# MCU.net
KiCad netlist of a schematic drawn in Altium Designer
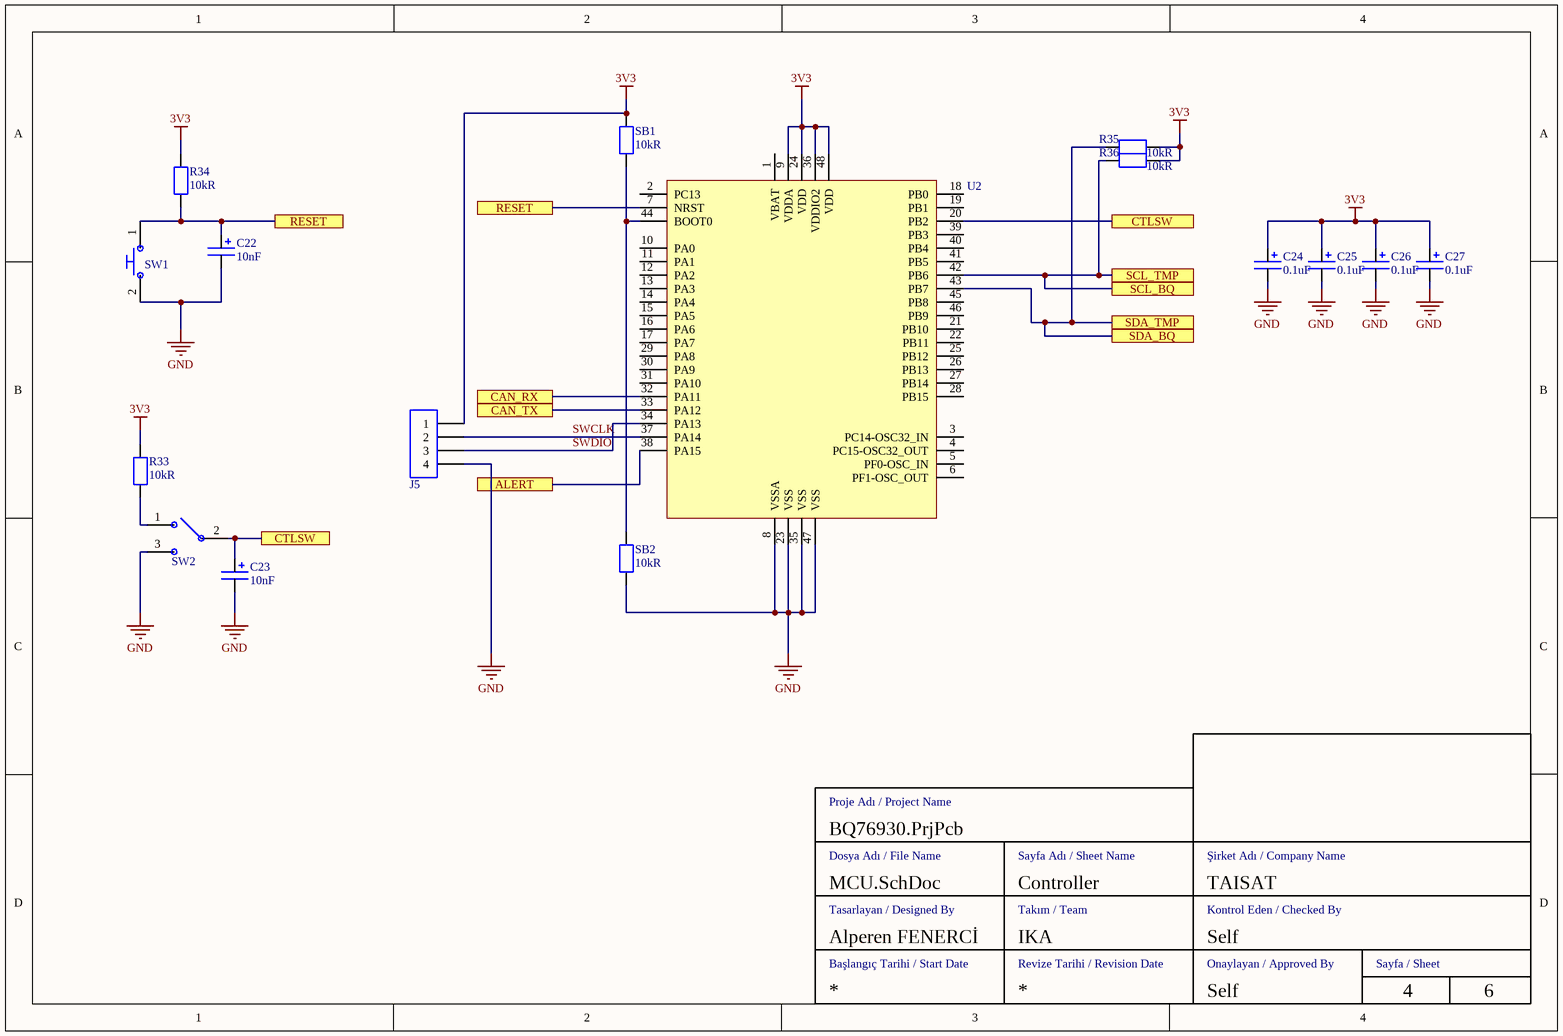
[diagram p0: MCU.SchDoc]

(export (version "E")
  (design (tool "Eeschema 10.0.6"))
  (components
    (comp (ref "C22")
      (value "10nF")
      (footprint "CAP 0603")
      (description "Multilayer Ceramic Capacitor")
      (fields (field (name "Comment") "CAP 0603"))
      (libsource (lib "Kaptanyums Lib") (part "CAP 0603"))
    )
    (comp (ref "C23")
      (value "10nF")
      (footprint "CAP 0603")
      (description "Multilayer Ceramic Capacitor")
      (fields (field (name "Comment") "CAP 0603"))
      (libsource (lib "Kaptanyums Lib") (part "CAP 0603"))
    )
    (comp (ref "C24")
      (value "0.1uF")
      (footprint "CAP 0603")
      (description "Multilayer Ceramic Capacitor")
      (fields (field (name "Comment") "CAP 0603"))
      (libsource (lib "Kaptanyums Lib") (part "CAP 0603"))
    )
    (comp (ref "C25")
      (value "0.1uF")
      (footprint "CAP 0603")
      (description "Multilayer Ceramic Capacitor")
      (fields (field (name "Comment") "CAP 0603"))
      (libsource (lib "Kaptanyums Lib") (part "CAP 0603"))
    )
    (comp (ref "C26")
      (value "0.1uF")
      (footprint "CAP 0603")
      (description "Multilayer Ceramic Capacitor")
      (fields (field (name "Comment") "CAP 0603"))
      (libsource (lib "Kaptanyums Lib") (part "CAP 0603"))
    )
    (comp (ref "C27")
      (value "0.1uF")
      (footprint "CAP 0603")
      (description "Multilayer Ceramic Capacitor")
      (fields (field (name "Comment") "CAP 0603"))
      (libsource (lib "Kaptanyums Lib") (part "CAP 0603"))
    )
    (comp (ref "J5")
      (value "146285-4")
      (footprint "HMATHT00C41")
      (description "Header for PCB")
      (libsource (lib "Kaptanyums Lib") (part "HMATHT00C41"))
    )
    (comp (ref "R33")
      (value "10kR")
      (footprint "RESISTOR 0603")
      (description "SMD Chip Resistor")
      (fields (field (name "Comment") "RES 0603"))
      (libsource (lib "Kaptanyums Lib") (part "RES 0603"))
    )
    (comp (ref "R34")
      (value "10kR")
      (footprint "RESISTOR 0603")
      (description "SMD Chip Resistor")
      (fields (field (name "Comment") "RES 0603"))
      (libsource (lib "Kaptanyums Lib") (part "RES 0603"))
    )
    (comp (ref "R35")
      (value "10kR")
      (footprint "RESISTOR 0603")
      (description "SMD Chip Resistor")
      (fields (field (name "Comment") "RES 0603"))
      (libsource (lib "Kaptanyums Lib") (part "RES 0603"))
    )
    (comp (ref "R36")
      (value "10kR")
      (footprint "RESISTOR 0603")
      (description "SMD Chip Resistor")
      (fields (field (name "Comment") "RES 0603"))
      (libsource (lib "Kaptanyums Lib") (part "RES 0603"))
    )
    (comp (ref "SB1")
      (value "10kR")
      (footprint "RESISTOR 0603")
      (description "SMD Chip Resistor")
      (fields (field (name "Comment") "RES 0603"))
      (libsource (lib "Kaptanyums Lib") (part "RES 0603"))
    )
    (comp (ref "SB2")
      (value "10kR")
      (footprint "RESISTOR 0603")
      (description "SMD Chip Resistor")
      (fields (field (name "Comment") "RES 0603"))
      (libsource (lib "Kaptanyums Lib") (part "RES 0603"))
    )
    (comp (ref "SW1")
      (value "DS1042-03")
      (footprint "SWITCH-6X6")
      (description "Switch")
      (libsource (lib "Kaptanyums Lib") (part "DS1042-03"))
    )
    (comp (ref "SW2")
      (value "L-KLS7-SS-12F20A")
      (footprint "SPDT")
      (description "Switch")
      (libsource (lib "Kaptanyums Lib") (part "L-KLS7-SS-12F20A"))
    )
    (comp (ref "U2")
      (value "STM32F072C8")
      (footprint "LQFP48")
      (description "STM32 ARM Cortex M0")
      (libsource (lib "Kaptanyums Lib") (part "STM32F072C8"))
    )
  )
  (nets
    (net (code "1") (name "/ALERT") (class "Default")
      (node (ref "U2") (pin "38") (pinfunction "PA15_38") (pintype "passive"))
    )
    (net (code "2") (name "/CAN_RX") (class "Default")
      (node (ref "U2") (pin "32") (pinfunction "PA11_32") (pintype "passive"))
    )
    (net (code "3") (name "/CAN_TX") (class "Default")
      (node (ref "U2") (pin "33") (pinfunction "PA12_33") (pintype "passive"))
    )
    (net (code "4") (name "/CTLSW") (class "Default")
      (node (ref "C23") (pin "1") (pinfunction "1_1") (pintype "passive"))
      (node (ref "SW2") (pin "2") (pinfunction "2_2") (pintype "passive"))
      (node (ref "U2") (pin "20") (pinfunction "PB2_20") (pintype "passive"))
    )
    (net (code "5") (name "/RESET") (class "Default")
      (node (ref "C22") (pin "1") (pinfunction "1_1") (pintype "passive"))
      (node (ref "R34") (pin "1") (pinfunction "1_1") (pintype "passive"))
      (node (ref "SW1") (pin "1") (pinfunction "1_1") (pintype "passive"))
      (node (ref "U2") (pin "7") (pinfunction "NRST_7") (pintype "passive"))
    )
    (net (code "6") (name "/SCL_BQ") (class "Default")
      (node (ref "R36") (pin "1") (pinfunction "1_1") (pintype "passive"))
      (node (ref "U2") (pin "42") (pinfunction "PB6_42") (pintype "passive"))
    )
    (net (code "7") (name "/SDA_BQ") (class "Default")
      (node (ref "R35") (pin "1") (pinfunction "1_1") (pintype "passive"))
      (node (ref "U2") (pin "43") (pinfunction "PB7_43") (pintype "passive"))
    )
    (net (code "8") (name "/SWCLK") (class "Default")
      (node (ref "J5") (pin "2") (pinfunction "2_2") (pintype "passive"))
      (node (ref "U2") (pin "37") (pinfunction "PA14_37") (pintype "passive"))
    )
    (net (code "9") (name "/SWDIO") (class "Default")
      (node (ref "J5") (pin "3") (pinfunction "3_3") (pintype "passive"))
      (node (ref "U2") (pin "34") (pinfunction "PA13_34") (pintype "passive"))
    )
    (net (code "10") (name "3V3") (class "Default")
      (node (ref "C24") (pin "1") (pinfunction "1_1") (pintype "passive"))
      (node (ref "C25") (pin "1") (pinfunction "1_1") (pintype "passive"))
      (node (ref "C26") (pin "1") (pinfunction "1_1") (pintype "passive"))
      (node (ref "C27") (pin "1") (pinfunction "1_1") (pintype "passive"))
      (node (ref "J5") (pin "1") (pinfunction "1_1") (pintype "passive"))
      (node (ref "R33") (pin "2") (pinfunction "2_2") (pintype "passive"))
      (node (ref "R34") (pin "2") (pinfunction "2_2") (pintype "passive"))
      (node (ref "R35") (pin "2") (pinfunction "2_2") (pintype "passive"))
      (node (ref "R36") (pin "2") (pinfunction "2_2") (pintype "passive"))
      (node (ref "SB1") (pin "2") (pinfunction "2_2") (pintype "passive"))
      (node (ref "U2") (pin "24") (pinfunction "VDD_24") (pintype "passive"))
      (node (ref "U2") (pin "36") (pinfunction "VDDIO2_36") (pintype "passive"))
      (node (ref "U2") (pin "48") (pinfunction "VDD_48") (pintype "passive"))
      (node (ref "U2") (pin "9") (pinfunction "VDDA_9") (pintype "passive"))
    )
    (net (code "11") (name "GND") (class "Default")
      (node (ref "C22") (pin "2") (pinfunction "2_2") (pintype "passive"))
      (node (ref "C23") (pin "2") (pinfunction "2_2") (pintype "passive"))
      (node (ref "C24") (pin "2") (pinfunction "2_2") (pintype "passive"))
      (node (ref "C25") (pin "2") (pinfunction "2_2") (pintype "passive"))
      (node (ref "C26") (pin "2") (pinfunction "2_2") (pintype "passive"))
      (node (ref "C27") (pin "2") (pinfunction "2_2") (pintype "passive"))
      (node (ref "J5") (pin "4") (pinfunction "4_4") (pintype "passive"))
      (node (ref "SB2") (pin "1") (pinfunction "1_1") (pintype "passive"))
      (node (ref "SW1") (pin "2") (pinfunction "2_2") (pintype "passive"))
      (node (ref "SW2") (pin "3") (pinfunction "3_3") (pintype "passive"))
      (node (ref "U2") (pin "23") (pinfunction "VSS_23") (pintype "passive"))
      (node (ref "U2") (pin "35") (pinfunction "VSS_35") (pintype "passive"))
      (node (ref "U2") (pin "47") (pinfunction "VSS_47") (pintype "passive"))
      (node (ref "U2") (pin "8") (pinfunction "VSSA_8") (pintype "passive"))
    )
    (net (code "12") (name "Net-(R33-Pad1)") (class "Default")
      (node (ref "R33") (pin "1") (pinfunction "1_1") (pintype "passive"))
      (node (ref "SW2") (pin "1") (pinfunction "1_1") (pintype "passive"))
    )
    (net (code "13") (name "Net-(U2-BOOT0)") (class "Default")
      (node (ref "SB1") (pin "1") (pinfunction "1_1") (pintype "passive"))
      (node (ref "SB2") (pin "2") (pinfunction "2_2") (pintype "passive"))
      (node (ref "U2") (pin "44") (pinfunction "BOOT0_44") (pintype "passive"))
    )
    (net (code "14") (name "unconnected-(U2-PA0-Pad10)") (class "Default")
      (node (ref "U2") (pin "10") (pinfunction "PA0_10") (pintype "passive"))
    )
    (net (code "15") (name "unconnected-(U2-PA1-Pad11)") (class "Default")
      (node (ref "U2") (pin "11") (pinfunction "PA1_11") (pintype "passive"))
    )
    (net (code "16") (name "unconnected-(U2-PA2-Pad12)") (class "Default")
      (node (ref "U2") (pin "12") (pinfunction "PA2_12") (pintype "passive"))
    )
    (net (code "17") (name "unconnected-(U2-PA3-Pad13)") (class "Default")
      (node (ref "U2") (pin "13") (pinfunction "PA3_13") (pintype "passive"))
    )
    (net (code "18") (name "unconnected-(U2-PA4-Pad14)") (class "Default")
      (node (ref "U2") (pin "14") (pinfunction "PA4_14") (pintype "passive"))
    )
    (net (code "19") (name "unconnected-(U2-PA5-Pad15)") (class "Default")
      (node (ref "U2") (pin "15") (pinfunction "PA5_15") (pintype "passive"))
    )
    (net (code "20") (name "unconnected-(U2-PA6-Pad16)") (class "Default")
      (node (ref "U2") (pin "16") (pinfunction "PA6_16") (pintype "passive"))
    )
    (net (code "21") (name "unconnected-(U2-PA7-Pad17)") (class "Default")
      (node (ref "U2") (pin "17") (pinfunction "PA7_17") (pintype "passive"))
    )
    (net (code "22") (name "unconnected-(U2-PA8-Pad29)") (class "Default")
      (node (ref "U2") (pin "29") (pinfunction "PA8_29") (pintype "passive"))
    )
    (net (code "23") (name "unconnected-(U2-PA9-Pad30)") (class "Default")
      (node (ref "U2") (pin "30") (pinfunction "PA9_30") (pintype "passive"))
    )
    (net (code "24") (name "unconnected-(U2-PA10-Pad31)") (class "Default")
      (node (ref "U2") (pin "31") (pinfunction "PA10_31") (pintype "passive"))
    )
    (net (code "25") (name "unconnected-(U2-PB0-Pad18)") (class "Default")
      (node (ref "U2") (pin "18") (pinfunction "PB0_18") (pintype "passive"))
    )
    (net (code "26") (name "unconnected-(U2-PB1-Pad19)") (class "Default")
      (node (ref "U2") (pin "19") (pinfunction "PB1_19") (pintype "passive"))
    )
    (net (code "27") (name "unconnected-(U2-PB3-Pad39)") (class "Default")
      (node (ref "U2") (pin "39") (pinfunction "PB3_39") (pintype "passive"))
    )
    (net (code "28") (name "unconnected-(U2-PB4-Pad40)") (class "Default")
      (node (ref "U2") (pin "40") (pinfunction "PB4_40") (pintype "passive"))
    )
    (net (code "29") (name "unconnected-(U2-PB5-Pad41)") (class "Default")
      (node (ref "U2") (pin "41") (pinfunction "PB5_41") (pintype "passive"))
    )
    (net (code "30") (name "unconnected-(U2-PB8-Pad45)") (class "Default")
      (node (ref "U2") (pin "45") (pinfunction "PB8_45") (pintype "passive"))
    )
    (net (code "31") (name "unconnected-(U2-PB9-Pad46)") (class "Default")
      (node (ref "U2") (pin "46") (pinfunction "PB9_46") (pintype "passive"))
    )
    (net (code "32") (name "unconnected-(U2-PB10-Pad21)") (class "Default")
      (node (ref "U2") (pin "21") (pinfunction "PB10_21") (pintype "passive"))
    )
    (net (code "33") (name "unconnected-(U2-PB11-Pad22)") (class "Default")
      (node (ref "U2") (pin "22") (pinfunction "PB11_22") (pintype "passive"))
    )
    (net (code "34") (name "unconnected-(U2-PB12-Pad25)") (class "Default")
      (node (ref "U2") (pin "25") (pinfunction "PB12_25") (pintype "passive"))
    )
    (net (code "35") (name "unconnected-(U2-PB13-Pad26)") (class "Default")
      (node (ref "U2") (pin "26") (pinfunction "PB13_26") (pintype "passive"))
    )
    (net (code "36") (name "unconnected-(U2-PB14-Pad27)") (class "Default")
      (node (ref "U2") (pin "27") (pinfunction "PB14_27") (pintype "passive"))
    )
    (net (code "37") (name "unconnected-(U2-PB15-Pad28)") (class "Default")
      (node (ref "U2") (pin "28") (pinfunction "PB15_28") (pintype "passive"))
    )
    (net (code "38") (name "unconnected-(U2-PC13-Pad2)") (class "Default")
      (node (ref "U2") (pin "2") (pinfunction "PC13_2") (pintype "passive"))
    )
    (net (code "39") (name "unconnected-(U2-PC14-OSC32_IN-Pad3)") (class "Default")
      (node (ref "U2") (pin "3") (pinfunction "PC14-OSC32_IN_3") (pintype "passive"))
    )
    (net (code "40") (name "unconnected-(U2-PC15-OSC32_OUT-Pad4)") (class "Default")
      (node (ref "U2") (pin "4") (pinfunction "PC15-OSC32_OUT_4") (pintype "passive"))
    )
    (net (code "41") (name "unconnected-(U2-PF0-OSC_IN-Pad5)") (class "Default")
      (node (ref "U2") (pin "5") (pinfunction "PF0-OSC_IN_5") (pintype "passive"))
    )
    (net (code "42") (name "unconnected-(U2-PF1-OSC_OUT-Pad6)") (class "Default")
      (node (ref "U2") (pin "6") (pinfunction "PF1-OSC_OUT_6") (pintype "passive"))
    )
    (net (code "43") (name "unconnected-(U2-VBAT-Pad1)") (class "Default")
      (node (ref "U2") (pin "1") (pinfunction "VBAT_1") (pintype "passive"))
    )
  )
)
